# Power_Monitor.net
KiCad netlist of a schematic drawn in EAGLE
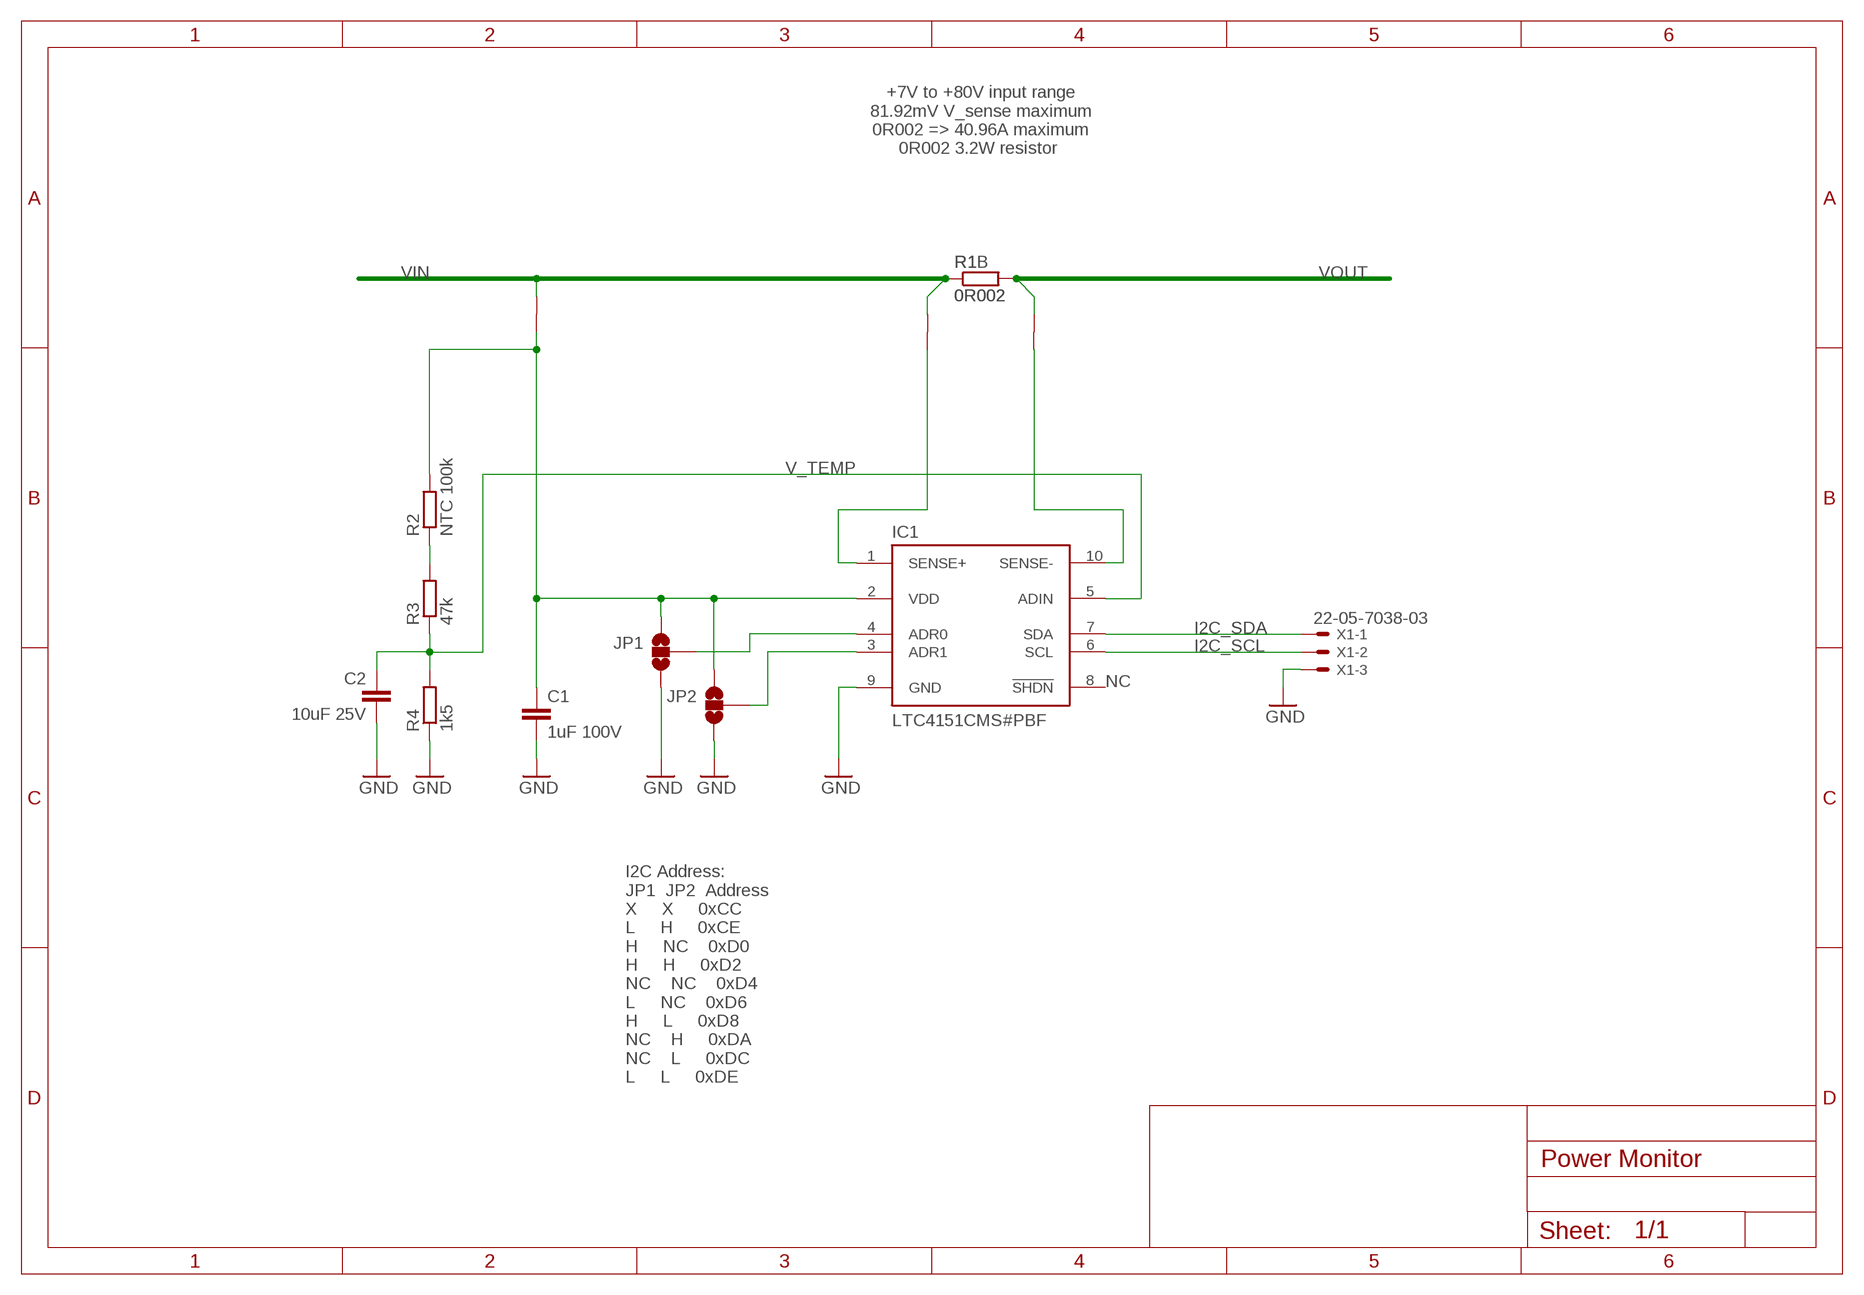
[diagram p0: schematic, sheet 1]

(export (version "E")
  (design (tool "Eeschema 10.0.6"))
  (components
    (comp (ref "C1")
      (value "1uF 100V")
      (footprint "eagle-import:C0603")
      (libsource (lib "eagle-import") (part "C-EUC0603"))
    )
    (comp (ref "C2")
      (value "10uF 25V")
      (footprint "eagle-import:C0603")
      (libsource (lib "eagle-import") (part "C-EUC0603"))
    )
    (comp (ref "IC1")
      (value "LTC4151CMS#PBF")
      (footprint "eagle-import:MSOP10")
      (libsource (lib "eagle-import") (part "LTC4151?MS"))
    )
    (comp (ref "JP1")
      (value "JUMPER-SMT_3_NO_SILK")
      (footprint "eagle-import:SMT-JUMPER_3_NO_SILK")
      (libsource (lib "eagle-import") (part "JUMPER-SMT_3_NO_SILK"))
    )
    (comp (ref "JP2")
      (value "JUMPER-SMT_3_NO_SILK")
      (footprint "eagle-import:SMT-JUMPER_3_NO_SILK")
      (libsource (lib "eagle-import") (part "JUMPER-SMT_3_NO_SILK"))
    )
    (comp (ref "R1")
      (value "0R002")
      (footprint "eagle-import:R2512")
      (libsource (lib "eagle-import") (part "R-EU_R2512"))
    )
    (comp (ref "R1B")
      (value "0R002")
      (footprint "eagle-import:R2512")
      (libsource (lib "eagle-import") (part "R-EU_R2512"))
    )
    (comp (ref "R2")
      (value "NTC 100k")
      (footprint "eagle-import:R0603")
      (libsource (lib "eagle-import") (part "R-EU_R0603"))
    )
    (comp (ref "R3")
      (value "47k")
      (footprint "eagle-import:R0603")
      (libsource (lib "eagle-import") (part "R-EU_R0603"))
    )
    (comp (ref "R4")
      (value "1k5")
      (footprint "eagle-import:R0603")
      (libsource (lib "eagle-import") (part "R-EU_R0603"))
    )
    (comp (ref "U$2")
      (value "SHORT-002")
      (footprint "eagle-import:2X2")
      (libsource (lib "eagle-import") (part "SHORT-002"))
    )
    (comp (ref "U$3")
      (value "SHORT-002")
      (footprint "eagle-import:2X2")
      (libsource (lib "eagle-import") (part "SHORT-002"))
    )
    (comp (ref "U$4")
      (value "SHORT-002")
      (footprint "eagle-import:2X2")
      (libsource (lib "eagle-import") (part "SHORT-002"))
    )
    (comp (ref "X1")
      (value "22-05-7038-03")
      (footprint "eagle-import:7395-03")
      (libsource (lib "eagle-import") (part "22-?-0305-7038"))
    )
  )
  (nets
    (net (code "1") (name "/I2C_SCL") (class "Default")
      (node (ref "IC1") (pin "6") (pinfunction "SCL_6") (pintype "bidirectional"))
      (node (ref "X1") (pin "2") (pinfunction "S_2") (pintype "passive"))
    )
    (net (code "2") (name "/I2C_SDA") (class "Default")
      (node (ref "IC1") (pin "7") (pinfunction "SDA_7") (pintype "bidirectional"))
      (node (ref "X1") (pin "1") (pinfunction "S_1") (pintype "passive"))
    )
    (net (code "3") (name "/VIN") (class "Default")
      (node (ref "R1") (pin "1") (pinfunction "1_1") (pintype "passive"))
      (node (ref "R1B") (pin "1") (pinfunction "1_1") (pintype "passive"))
      (node (ref "U$2") (pin "2") (pinfunction "P$2_2") (pintype "bidirectional"))
      (node (ref "U$4") (pin "2") (pinfunction "P$2_2") (pintype "bidirectional"))
    )
    (net (code "4") (name "/VOUT") (class "Default")
      (node (ref "R1") (pin "2") (pinfunction "2_2") (pintype "passive"))
      (node (ref "R1B") (pin "2") (pinfunction "2_2") (pintype "passive"))
      (node (ref "U$3") (pin "2") (pinfunction "P$2_2") (pintype "bidirectional"))
    )
    (net (code "5") (name "/V_TEMP") (class "Default")
      (node (ref "C2") (pin "1") (pinfunction "1_1") (pintype "passive"))
      (node (ref "IC1") (pin "5") (pinfunction "ADIN_5") (pintype "bidirectional"))
      (node (ref "R3") (pin "1") (pinfunction "1_1") (pintype "passive"))
      (node (ref "R4") (pin "2") (pinfunction "2_2") (pintype "passive"))
    )
    (net (code "6") (name "GND") (class "Default")
      (node (ref "C1") (pin "2") (pinfunction "2_2") (pintype "passive"))
      (node (ref "C2") (pin "2") (pinfunction "2_2") (pintype "passive"))
      (node (ref "IC1") (pin "9") (pinfunction "GND_9") (pintype "power_in"))
      (node (ref "JP1") (pin "3") (pinfunction "3_3") (pintype "passive"))
      (node (ref "JP2") (pin "3") (pinfunction "3_3") (pintype "passive"))
      (node (ref "R4") (pin "1") (pinfunction "1_1") (pintype "passive"))
      (node (ref "X1") (pin "3") (pinfunction "S_3") (pintype "passive"))
    )
    (net (code "7") (name "Net-(IC1-ADR0)") (class "Default")
      (node (ref "IC1") (pin "4") (pinfunction "ADR0_4") (pintype "bidirectional"))
      (node (ref "JP1") (pin "2") (pinfunction "2_2") (pintype "passive"))
    )
    (net (code "8") (name "Net-(IC1-ADR1)") (class "Default")
      (node (ref "IC1") (pin "3") (pinfunction "ADR1_3") (pintype "bidirectional"))
      (node (ref "JP2") (pin "2") (pinfunction "2_2") (pintype "passive"))
    )
    (net (code "9") (name "Net-(IC1-SENSE+)") (class "Default")
      (node (ref "IC1") (pin "1") (pinfunction "SENSE+_1") (pintype "bidirectional"))
      (node (ref "U$2") (pin "1") (pinfunction "P$1_1") (pintype "bidirectional"))
    )
    (net (code "10") (name "Net-(IC1-SENSE-)") (class "Default")
      (node (ref "IC1") (pin "10") (pinfunction "SENSE-_10") (pintype "bidirectional"))
      (node (ref "U$3") (pin "1") (pinfunction "P$1_1") (pintype "bidirectional"))
    )
    (net (code "11") (name "Net-(IC1-VDD)") (class "Default")
      (node (ref "C1") (pin "1") (pinfunction "1_1") (pintype "passive"))
      (node (ref "IC1") (pin "2") (pinfunction "VDD_2") (pintype "power_in"))
      (node (ref "JP1") (pin "1") (pinfunction "1_1") (pintype "passive"))
      (node (ref "JP2") (pin "1") (pinfunction "1_1") (pintype "passive"))
      (node (ref "R2") (pin "2") (pinfunction "2_2") (pintype "passive"))
      (node (ref "U$4") (pin "1") (pinfunction "P$1_1") (pintype "bidirectional"))
    )
    (net (code "12") (name "Net-(R2-Pad1)") (class "Default")
      (node (ref "R2") (pin "1") (pinfunction "1_1") (pintype "passive"))
      (node (ref "R3") (pin "2") (pinfunction "2_2") (pintype "passive"))
    )
    (net (code "13") (name "unconnected-(IC1-~{SHDN}-Pad8)") (class "Default")
      (node (ref "IC1") (pin "8") (pinfunction "~{SHDN}_8") (pintype "input"))
    )
  )
)
